# plant-sense.net
KiCad netlist of a schematic drawn in EAGLE
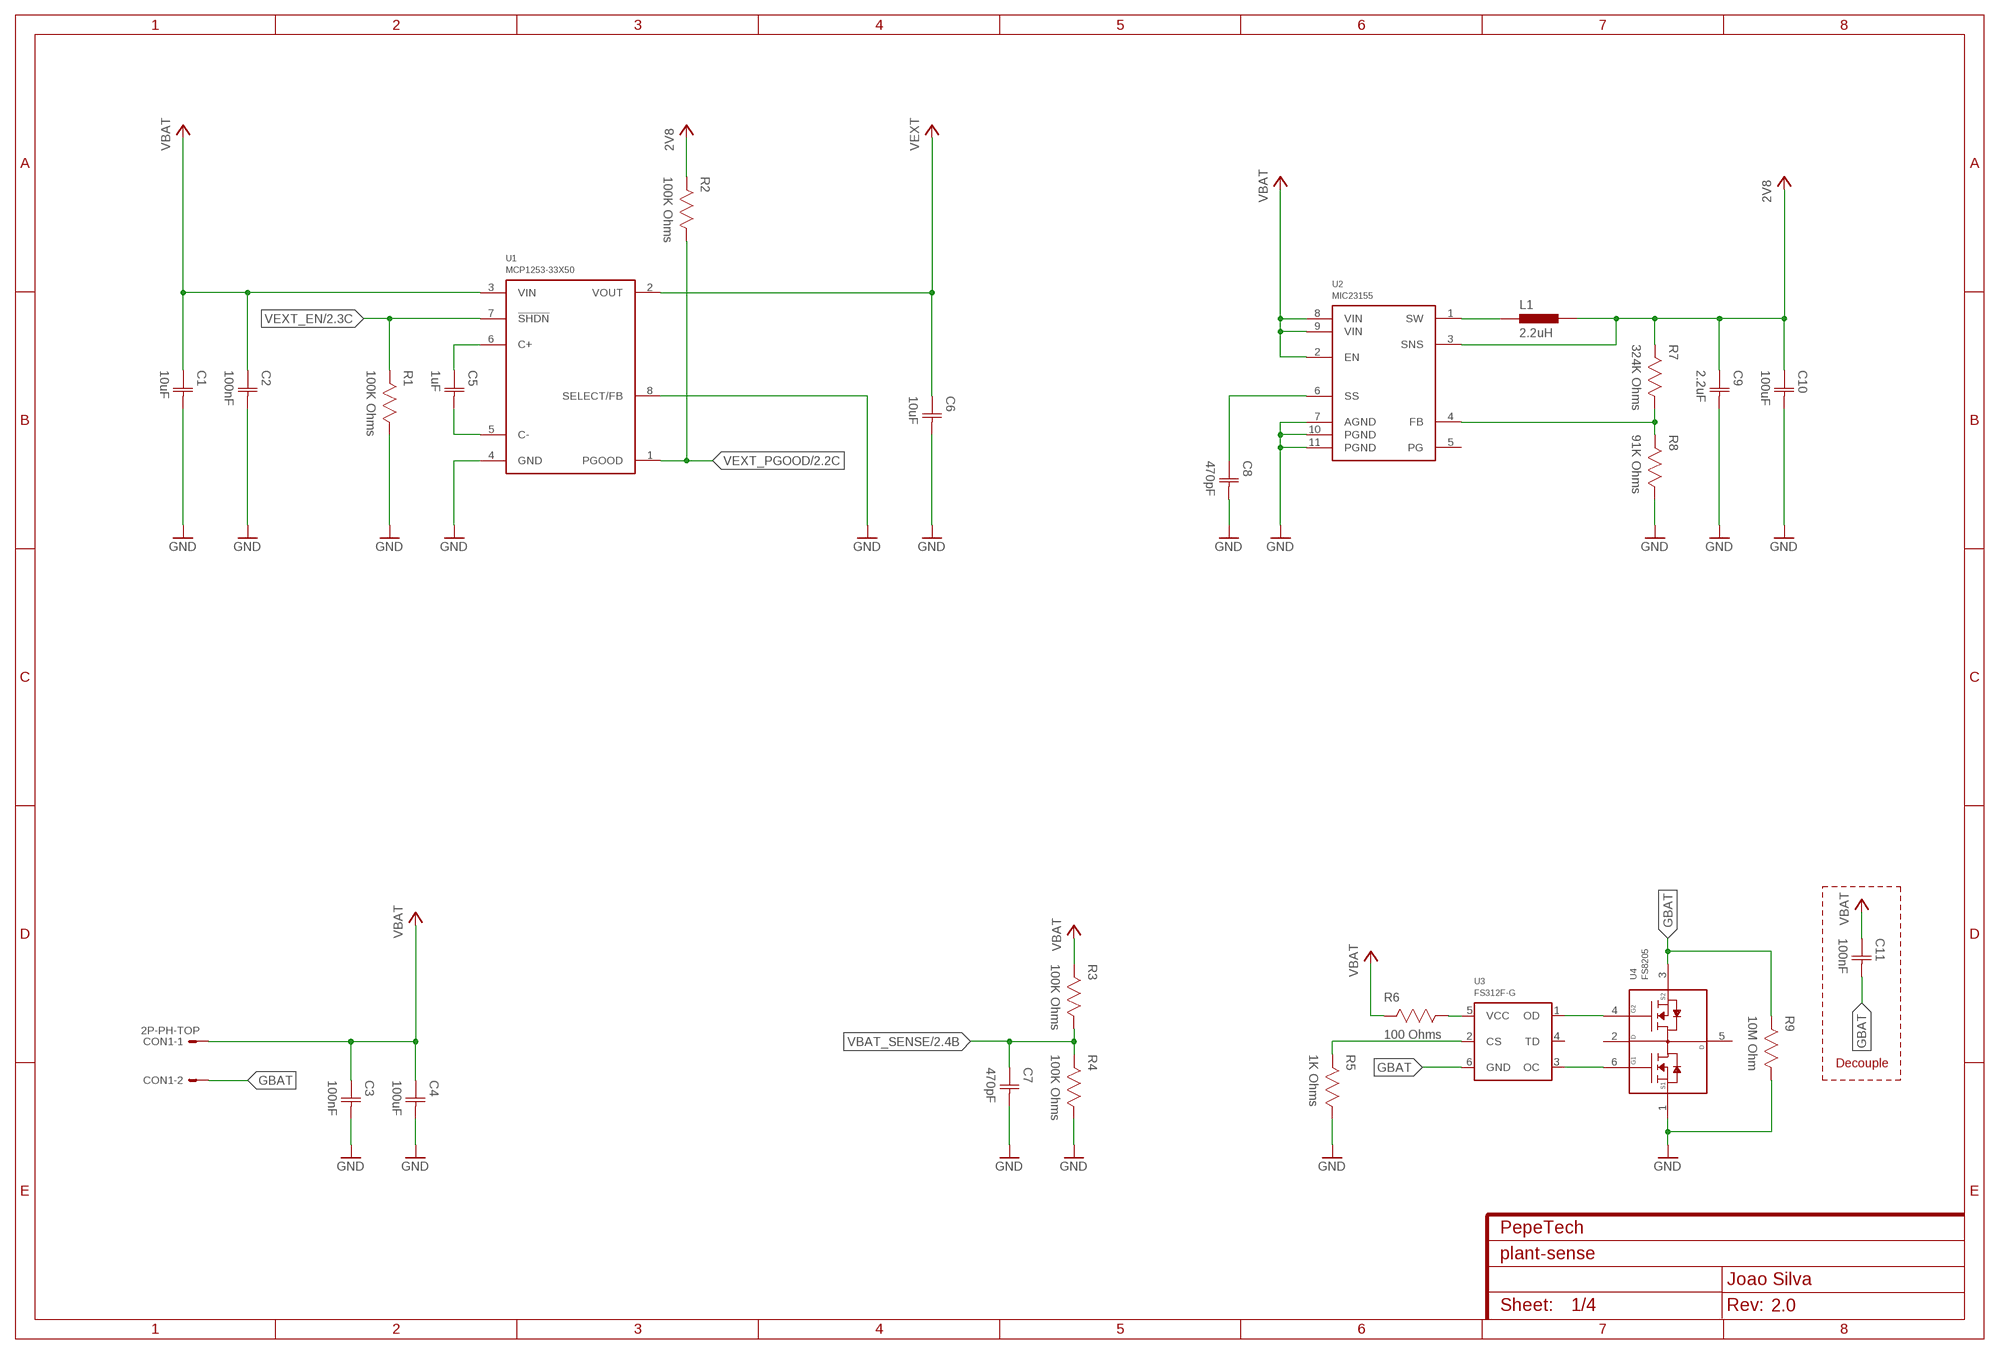
[diagram p0: schematic, sheet 1]
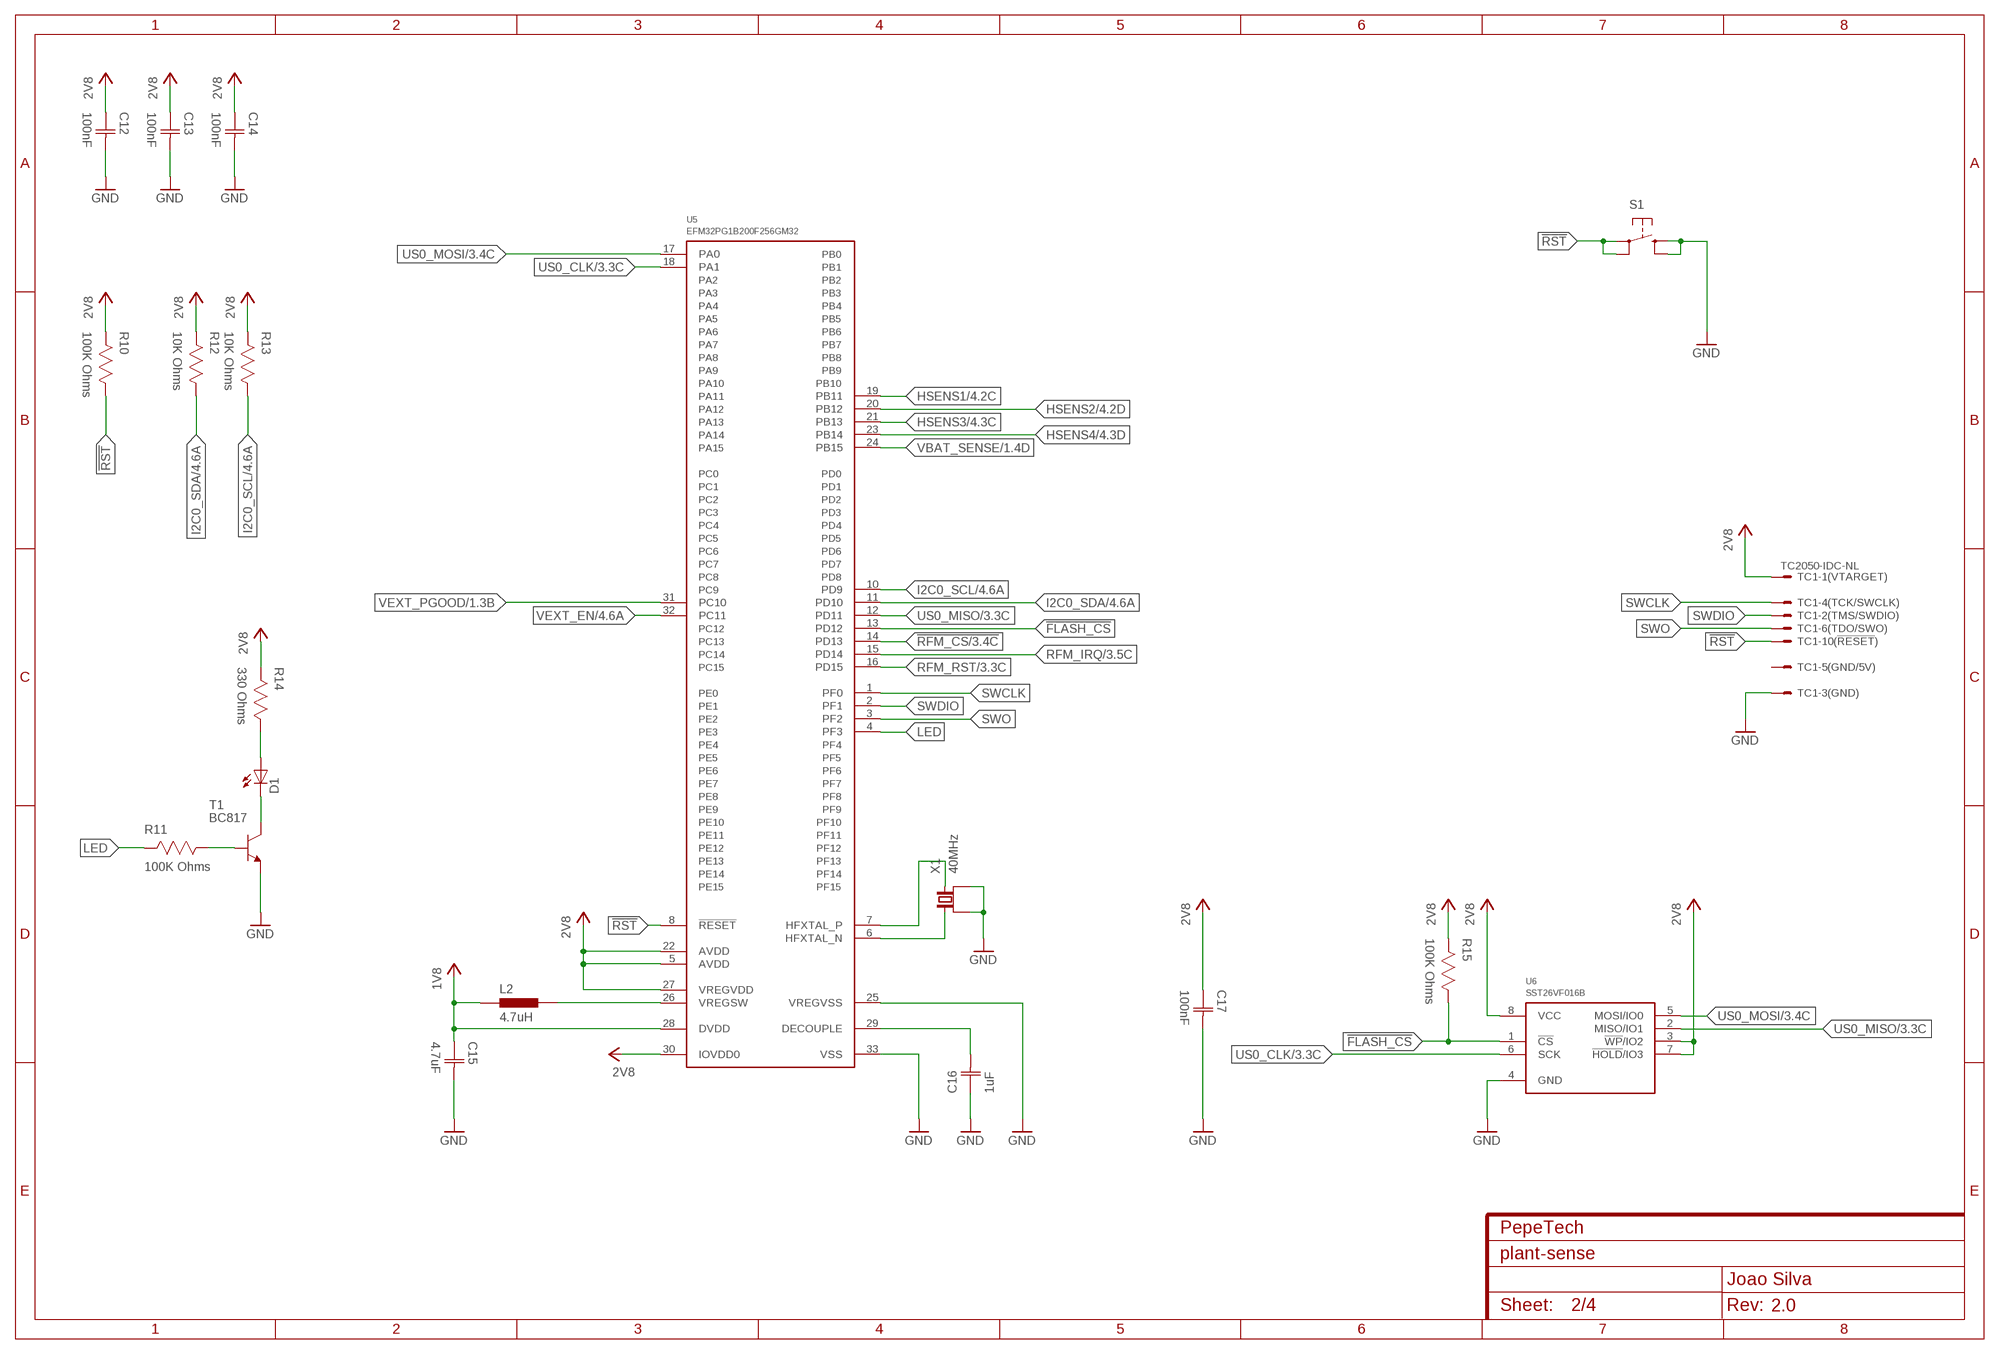
[diagram p1: schematic, sheet 2]
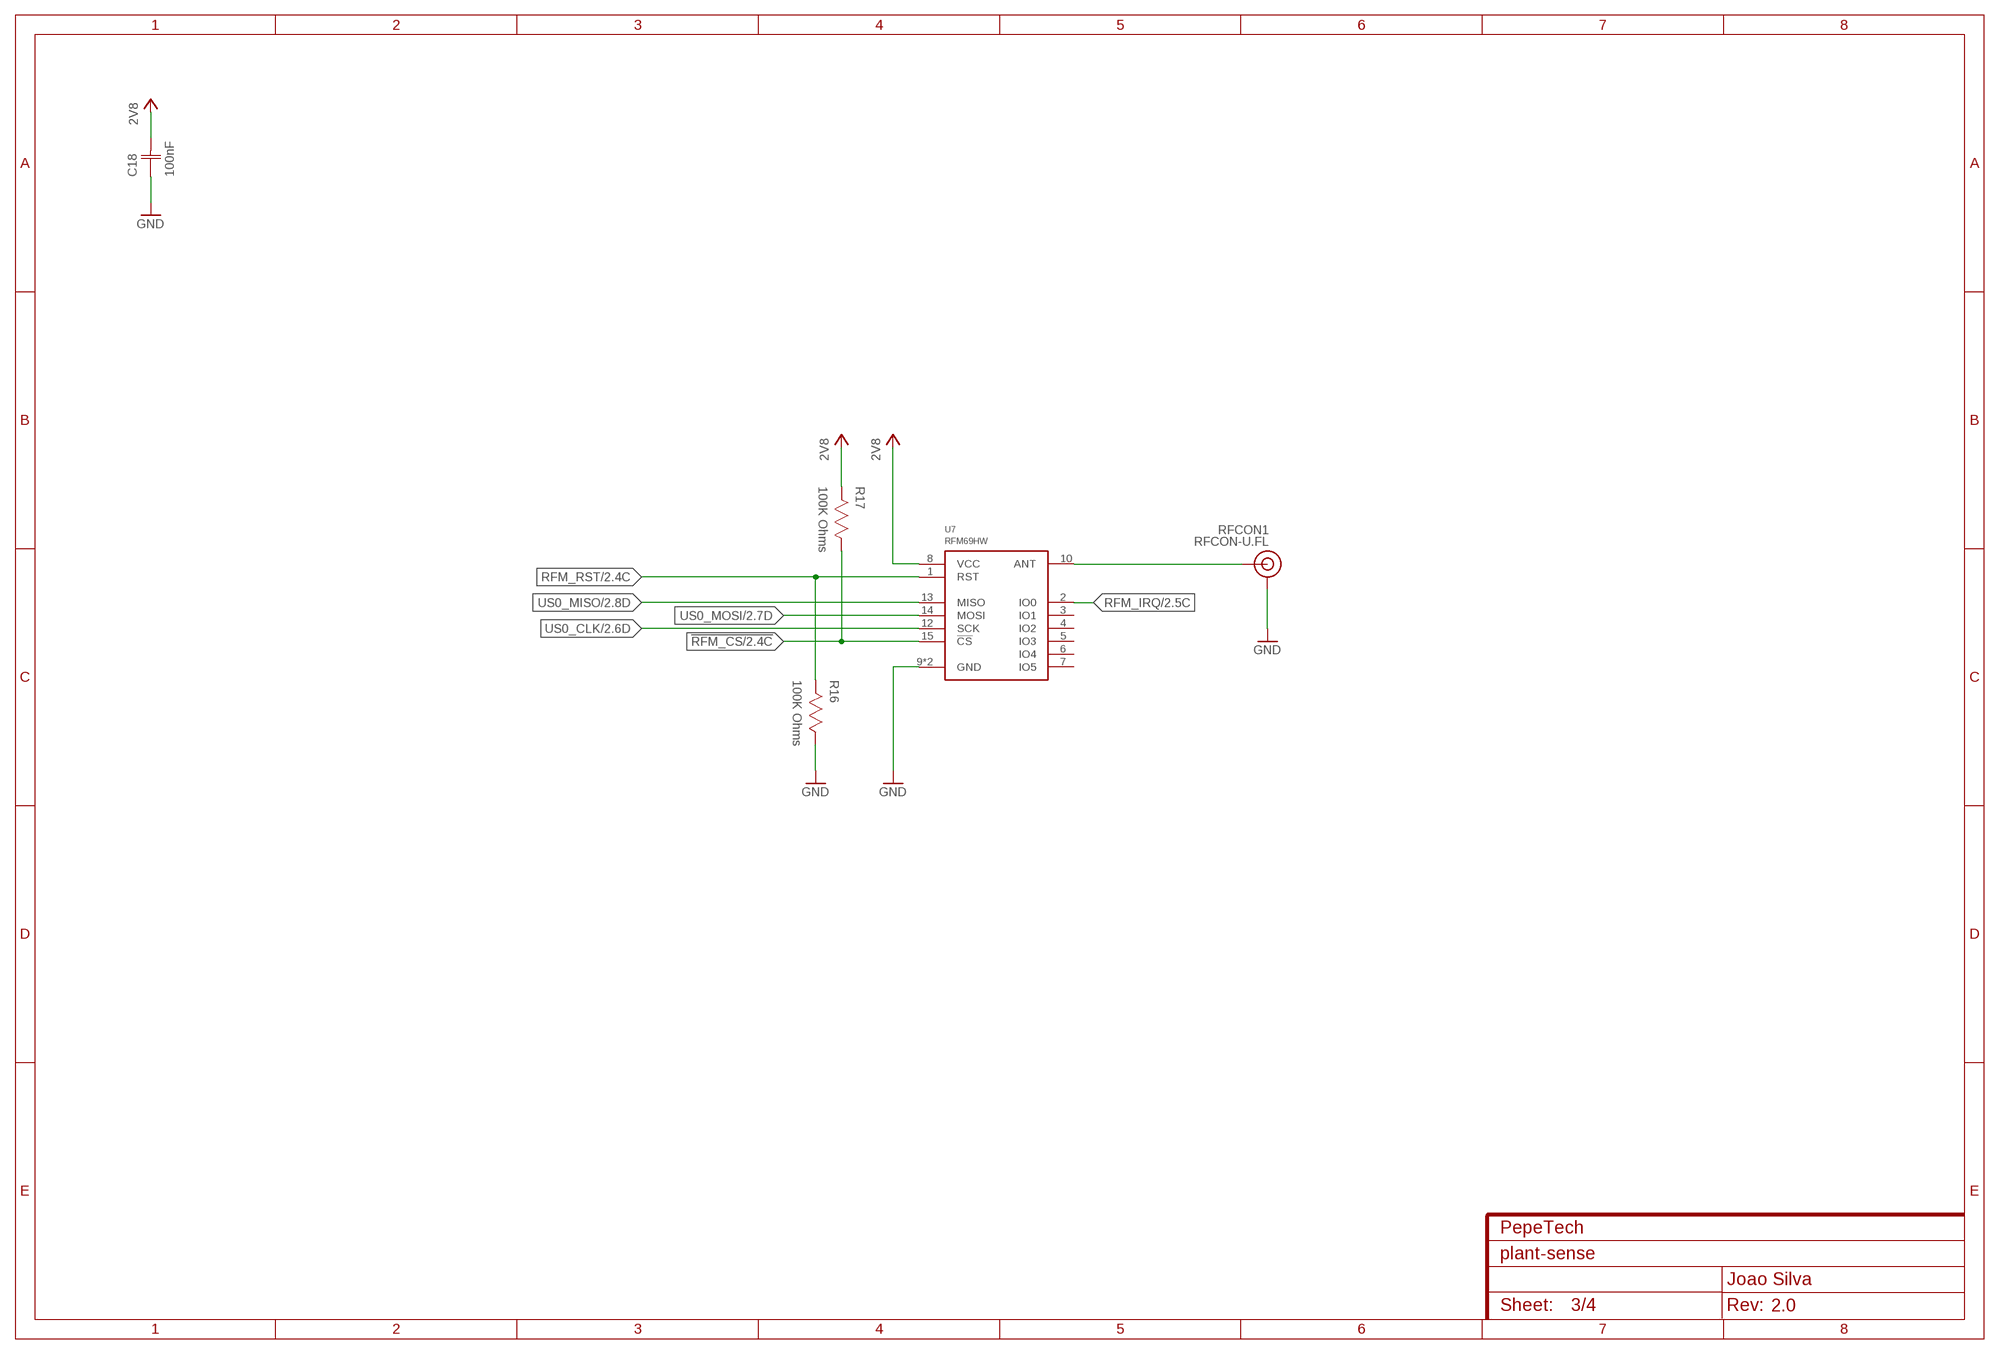
[diagram p2: schematic, sheet 3]
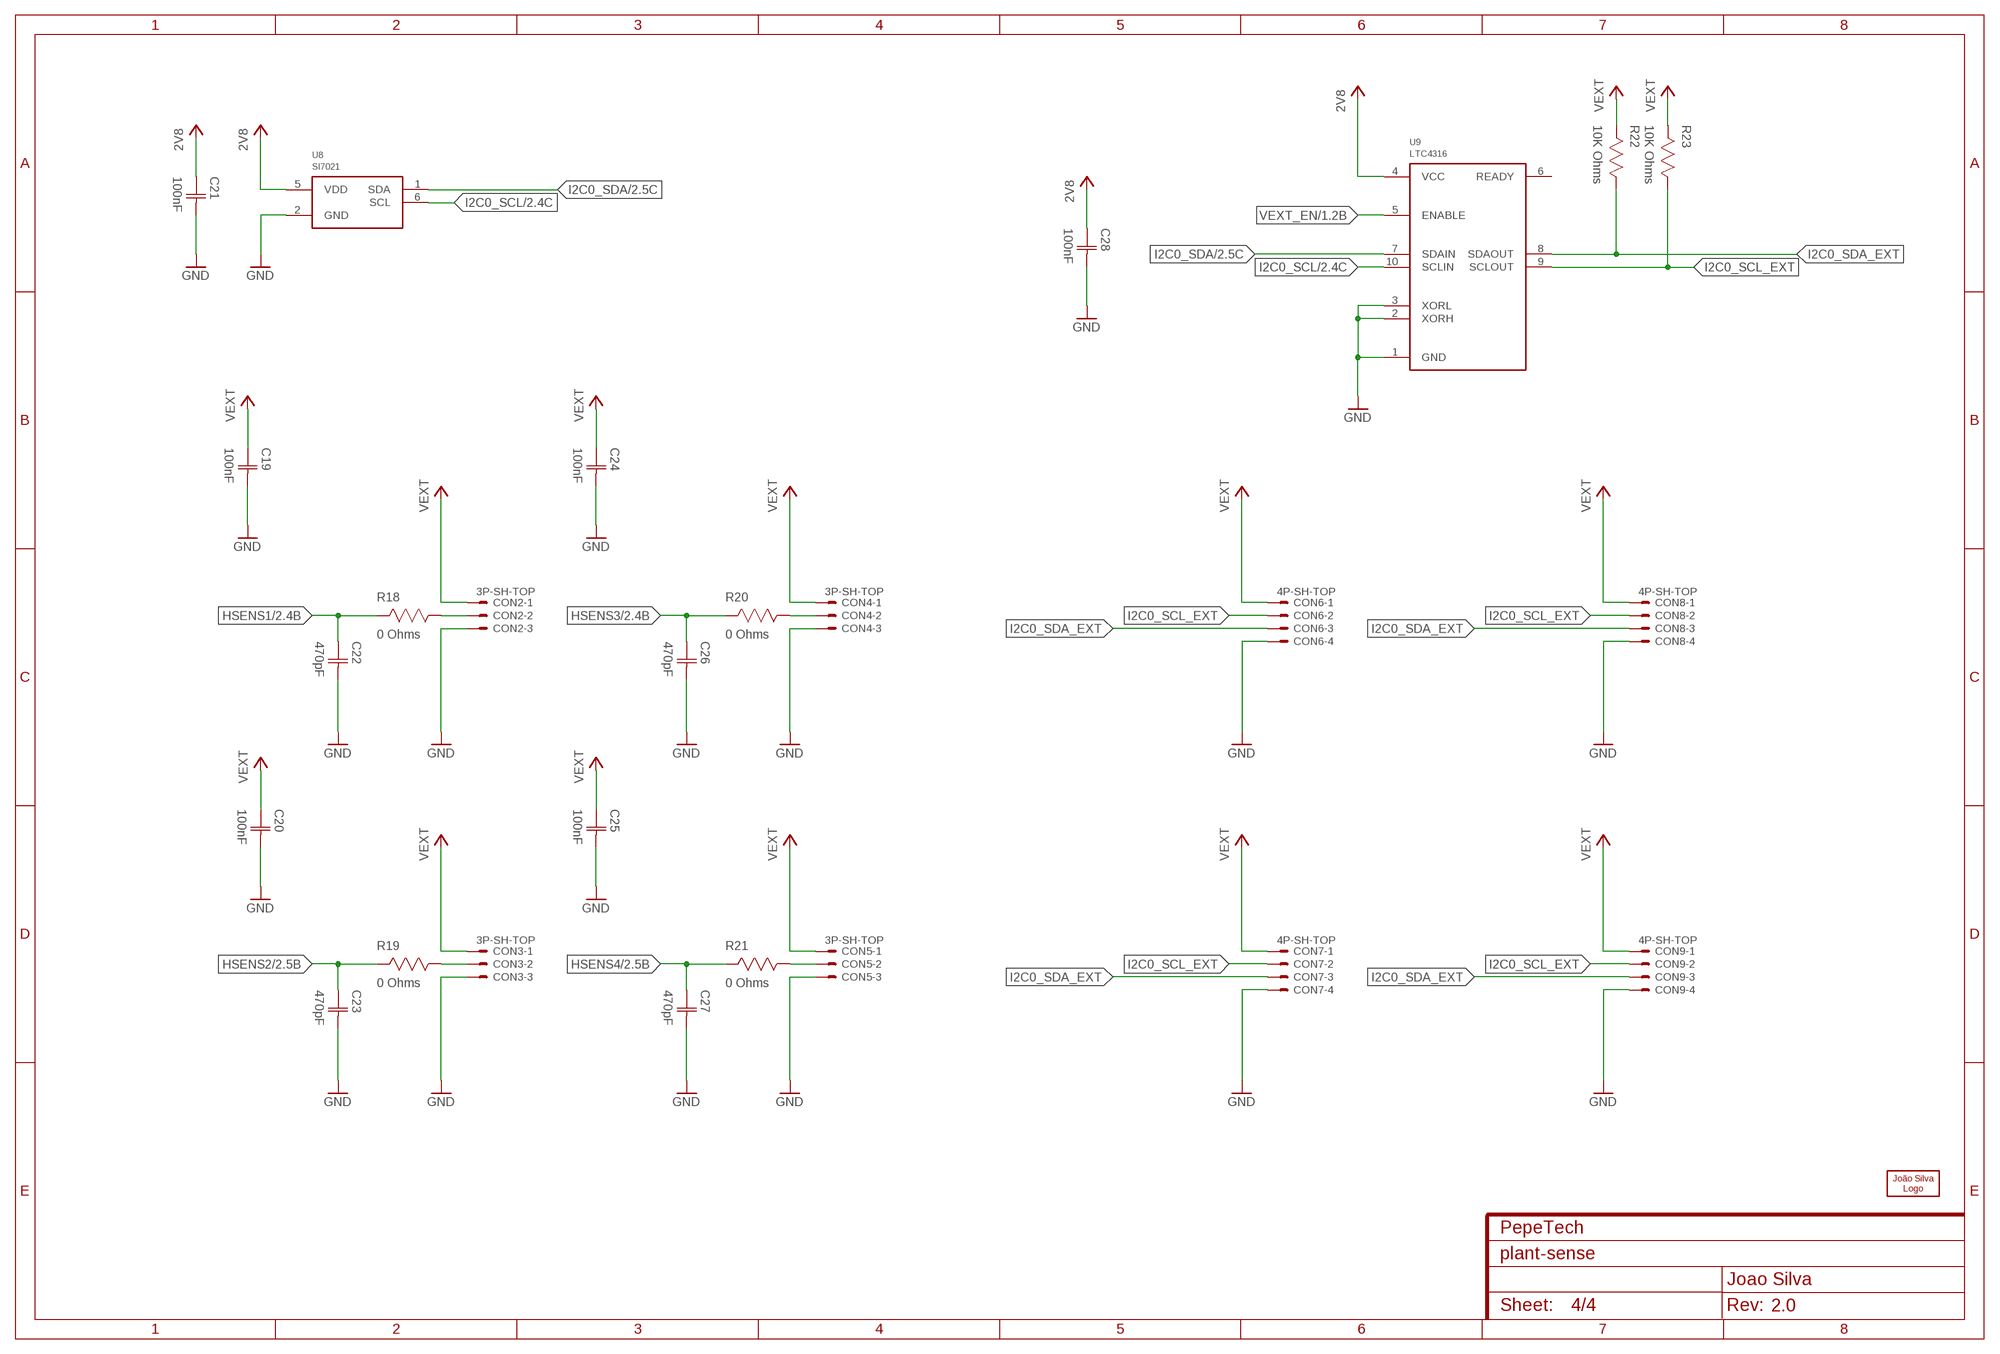
[diagram p3: schematic, sheet 4]

(export (version "E")
  (design (tool "Eeschema 10.0.6"))
  (components
    (comp (ref "C1")
      (value "10uF")
      (footprint "eagle-import:CAP0603")
      (libsource (lib "eagle-import") (part "CAPACITOR-0603"))
    )
    (comp (ref "C2")
      (value "100nF")
      (footprint "eagle-import:CAP0603")
      (libsource (lib "eagle-import") (part "CAPACITOR-0603"))
    )
    (comp (ref "C3")
      (value "100nF")
      (footprint "eagle-import:CAP0603")
      (libsource (lib "eagle-import") (part "CAPACITOR-0603"))
    )
    (comp (ref "C4")
      (value "100uF")
      (footprint "eagle-import:CAP1206")
      (libsource (lib "eagle-import") (part "CAPACITOR-1206"))
    )
    (comp (ref "C5")
      (value "1uF")
      (footprint "eagle-import:CAP0603")
      (libsource (lib "eagle-import") (part "CAPACITOR-0603"))
    )
    (comp (ref "C6")
      (value "10uF")
      (footprint "eagle-import:CAP0603")
      (libsource (lib "eagle-import") (part "CAPACITOR-0603"))
    )
    (comp (ref "C7")
      (value "470pF")
      (footprint "eagle-import:CAP0603")
      (libsource (lib "eagle-import") (part "CAPACITOR-0603"))
    )
    (comp (ref "C8")
      (value "470pF")
      (footprint "eagle-import:CAP0603")
      (libsource (lib "eagle-import") (part "CAPACITOR-0603"))
    )
    (comp (ref "C9")
      (value "2.2uF")
      (footprint "eagle-import:CAP0603")
      (libsource (lib "eagle-import") (part "CAPACITOR-0603"))
    )
    (comp (ref "C10")
      (value "100uF")
      (footprint "eagle-import:CAP1206")
      (libsource (lib "eagle-import") (part "CAPACITOR-1206"))
    )
    (comp (ref "C11")
      (value "100nF")
      (footprint "eagle-import:CAP0603")
      (libsource (lib "eagle-import") (part "CAPACITOR-0603"))
    )
    (comp (ref "CON1")
      (value "2P-PH-TOP")
      (footprint "eagle-import:PH-02-TOP")
      (libsource (lib "eagle-import") (part "2P-PH-TOP"))
    )
    (comp (ref "L1")
      (value "2.2uH")
      (footprint "eagle-import:IND0805")
      (libsource (lib "eagle-import") (part "INDUCTOR-0805"))
    )
    (comp (ref "R1")
      (value "100K Ohms")
      (footprint "eagle-import:RES0603")
      (libsource (lib "eagle-import") (part "RESISTOR-0603"))
    )
    (comp (ref "R2")
      (value "100K Ohms")
      (footprint "eagle-import:RES0603")
      (libsource (lib "eagle-import") (part "RESISTOR-0603"))
    )
    (comp (ref "R3")
      (value "100K Ohms")
      (footprint "eagle-import:RES0603")
      (libsource (lib "eagle-import") (part "RESISTOR-0603"))
    )
    (comp (ref "R4")
      (value "100K Ohms")
      (footprint "eagle-import:RES0603")
      (libsource (lib "eagle-import") (part "RESISTOR-0603"))
    )
    (comp (ref "R5")
      (value "1K Ohms")
      (footprint "eagle-import:RES0603")
      (libsource (lib "eagle-import") (part "RESISTOR-0603"))
    )
    (comp (ref "R6")
      (value "100 Ohms")
      (footprint "eagle-import:RES0603")
      (libsource (lib "eagle-import") (part "RESISTOR-0603"))
    )
    (comp (ref "R7")
      (value "324K Ohms")
      (footprint "eagle-import:RES0603")
      (libsource (lib "eagle-import") (part "RESISTOR-0603"))
    )
    (comp (ref "R8")
      (value "91K Ohms")
      (footprint "eagle-import:RES0603")
      (libsource (lib "eagle-import") (part "RESISTOR-0603"))
    )
    (comp (ref "R9")
      (value "10M Ohm")
      (footprint "eagle-import:RES0603")
      (libsource (lib "eagle-import") (part "RESISTOR-0603"))
    )
    (comp (ref "U1")
      (value "MCP1253-33X50")
      (footprint "eagle-import:MSOP8")
      (libsource (lib "eagle-import") (part "MCP1253-33X50"))
    )
    (comp (ref "U2")
      (value "MIC23155")
      (footprint "eagle-import:DFN10")
      (libsource (lib "eagle-import") (part "MIC23155"))
    )
    (comp (ref "U3")
      (value "FS312F-G")
      (footprint "eagle-import:SOT23-6")
      (libsource (lib "eagle-import") (part "FS312F-G"))
    )
    (comp (ref "U4")
      (value "FS8205")
      (footprint "eagle-import:SOT23-6")
      (libsource (lib "eagle-import") (part "FS8205"))
    )
    (comp (ref "C18")
      (value "100nF")
      (footprint "eagle-import:CAP0603")
      (libsource (lib "eagle-import") (part "CAPACITOR-0603"))
    )
    (comp (ref "R16")
      (value "100K Ohms")
      (footprint "eagle-import:RES0603")
      (libsource (lib "eagle-import") (part "RESISTOR-0603"))
    )
    (comp (ref "R17")
      (value "100K Ohms")
      (footprint "eagle-import:RES0603")
      (libsource (lib "eagle-import") (part "RESISTOR-0603"))
    )
    (comp (ref "RFCON1")
      (value "RFCON-U.FL")
      (footprint "eagle-import:U.FL")
      (libsource (lib "eagle-import") (part "RFCON-U.FL"))
    )
    (comp (ref "U7")
      (value "RFM69HW")
      (footprint "eagle-import:RFM69XW-XXXS2")
      (libsource (lib "eagle-import") (part "RFM69WH"))
    )
    (comp (ref "C19")
      (value "100nF")
      (footprint "eagle-import:CAP0603")
      (libsource (lib "eagle-import") (part "CAPACITOR-0603"))
    )
    (comp (ref "C20")
      (value "100nF")
      (footprint "eagle-import:CAP0603")
      (libsource (lib "eagle-import") (part "CAPACITOR-0603"))
    )
    (comp (ref "C21")
      (value "100nF")
      (footprint "eagle-import:CAP0603")
      (libsource (lib "eagle-import") (part "CAPACITOR-0603"))
    )
    (comp (ref "C22")
      (value "470pF")
      (footprint "eagle-import:CAP0603")
      (libsource (lib "eagle-import") (part "CAPACITOR-0603"))
    )
    (comp (ref "C23")
      (value "470pF")
      (footprint "eagle-import:CAP0603")
      (libsource (lib "eagle-import") (part "CAPACITOR-0603"))
    )
    (comp (ref "C24")
      (value "100nF")
      (footprint "eagle-import:CAP0603")
      (libsource (lib "eagle-import") (part "CAPACITOR-0603"))
    )
    (comp (ref "C25")
      (value "100nF")
      (footprint "eagle-import:CAP0603")
      (libsource (lib "eagle-import") (part "CAPACITOR-0603"))
    )
    (comp (ref "C26")
      (value "470pF")
      (footprint "eagle-import:CAP0603")
      (libsource (lib "eagle-import") (part "CAPACITOR-0603"))
    )
    (comp (ref "C27")
      (value "470pF")
      (footprint "eagle-import:CAP0603")
      (libsource (lib "eagle-import") (part "CAPACITOR-0603"))
    )
    (comp (ref "C28")
      (value "100nF")
      (footprint "eagle-import:CAP0603")
      (libsource (lib "eagle-import") (part "CAPACITOR-0603"))
    )
    (comp (ref "CON2")
      (value "3P-SH-TOP")
      (footprint "eagle-import:SH-03-TOP")
      (libsource (lib "eagle-import") (part "3P-SH-TOP"))
    )
    (comp (ref "CON3")
      (value "3P-SH-TOP")
      (footprint "eagle-import:SH-03-TOP")
      (libsource (lib "eagle-import") (part "3P-SH-TOP"))
    )
    (comp (ref "CON4")
      (value "3P-SH-TOP")
      (footprint "eagle-import:SH-03-TOP")
      (libsource (lib "eagle-import") (part "3P-SH-TOP"))
    )
    (comp (ref "CON5")
      (value "3P-SH-TOP")
      (footprint "eagle-import:SH-03-TOP")
      (libsource (lib "eagle-import") (part "3P-SH-TOP"))
    )
    (comp (ref "CON6")
      (value "4P-SH-TOP")
      (footprint "eagle-import:SH-04-TOP")
      (libsource (lib "eagle-import") (part "4P-SH-TOP"))
    )
    (comp (ref "CON7")
      (value "4P-SH-TOP")
      (footprint "eagle-import:SH-04-TOP")
      (libsource (lib "eagle-import") (part "4P-SH-TOP"))
    )
    (comp (ref "CON8")
      (value "4P-SH-TOP")
      (footprint "eagle-import:SH-04-TOP")
      (libsource (lib "eagle-import") (part "4P-SH-TOP"))
    )
    (comp (ref "CON9")
      (value "4P-SH-TOP")
      (footprint "eagle-import:SH-04-TOP")
      (libsource (lib "eagle-import") (part "4P-SH-TOP"))
    )
    (comp (ref "LOGO1")
      (value "JS-5MM")
      (footprint "eagle-import:JS_5MM")
      (libsource (lib "eagle-import") (part "JS-5MM"))
    )
    (comp (ref "R18")
      (value "0 Ohms")
      (footprint "eagle-import:RES0603")
      (libsource (lib "eagle-import") (part "RESISTOR-0603"))
    )
    (comp (ref "R19")
      (value "0 Ohms")
      (footprint "eagle-import:RES0603")
      (libsource (lib "eagle-import") (part "RESISTOR-0603"))
    )
    (comp (ref "R20")
      (value "0 Ohms")
      (footprint "eagle-import:RES0603")
      (libsource (lib "eagle-import") (part "RESISTOR-0603"))
    )
    (comp (ref "R21")
      (value "0 Ohms")
      (footprint "eagle-import:RES0603")
      (libsource (lib "eagle-import") (part "RESISTOR-0603"))
    )
    (comp (ref "R22")
      (value "10K Ohms")
      (footprint "eagle-import:RES0603")
      (libsource (lib "eagle-import") (part "RESISTOR-0603"))
    )
    (comp (ref "R23")
      (value "10K Ohms")
      (footprint "eagle-import:RES0603")
      (libsource (lib "eagle-import") (part "RESISTOR-0603"))
    )
    (comp (ref "U8")
      (value "SI7021")
      (footprint "eagle-import:DFN6")
      (libsource (lib "eagle-import") (part "SI7021"))
    )
    (comp (ref "U9")
      (value "LTC4316")
      (footprint "eagle-import:MSOP10")
      (libsource (lib "eagle-import") (part "LTC4316"))
    )
    (comp (ref "C12")
      (value "100nF")
      (footprint "eagle-import:CAP0603")
      (libsource (lib "eagle-import") (part "CAPACITOR-0603"))
    )
    (comp (ref "C13")
      (value "100nF")
      (footprint "eagle-import:CAP0603")
      (libsource (lib "eagle-import") (part "CAPACITOR-0603"))
    )
    (comp (ref "C14")
      (value "100nF")
      (footprint "eagle-import:CAP0603")
      (libsource (lib "eagle-import") (part "CAPACITOR-0603"))
    )
    (comp (ref "C15")
      (value "4.7uF")
      (footprint "eagle-import:CAP0603")
      (libsource (lib "eagle-import") (part "CAPACITOR-0603"))
    )
    (comp (ref "C16")
      (value "1uF")
      (footprint "eagle-import:CAP0603")
      (libsource (lib "eagle-import") (part "CAPACITOR-0603"))
    )
    (comp (ref "C17")
      (value "100nF")
      (footprint "eagle-import:CAP0603")
      (libsource (lib "eagle-import") (part "CAPACITOR-0603"))
    )
    (comp (ref "D1")
      (value "LED1206")
      (footprint "eagle-import:1206")
      (libsource (lib "eagle-import") (part "LED1206"))
    )
    (comp (ref "L2")
      (value "4.7uH")
      (footprint "eagle-import:IND0603")
      (libsource (lib "eagle-import") (part "INDUCTOR-0603"))
    )
    (comp (ref "R10")
      (value "100K Ohms")
      (footprint "eagle-import:RES0603")
      (libsource (lib "eagle-import") (part "RESISTOR-0603"))
    )
    (comp (ref "R11")
      (value "100K Ohms")
      (footprint "eagle-import:RES0603")
      (libsource (lib "eagle-import") (part "RESISTOR-0603"))
    )
    (comp (ref "R12")
      (value "10K Ohms")
      (footprint "eagle-import:RES0603")
      (libsource (lib "eagle-import") (part "RESISTOR-0603"))
    )
    (comp (ref "R13")
      (value "10K Ohms")
      (footprint "eagle-import:RES0603")
      (libsource (lib "eagle-import") (part "RESISTOR-0603"))
    )
    (comp (ref "R14")
      (value "330 Ohms")
      (footprint "eagle-import:RES0603")
      (libsource (lib "eagle-import") (part "RESISTOR-0603"))
    )
    (comp (ref "R15")
      (value "100K Ohms")
      (footprint "eagle-import:RES0603")
      (libsource (lib "eagle-import") (part "RESISTOR-0603"))
    )
    (comp (ref "S1")
      (value "TAC_SWITCHSMD")
      (footprint "eagle-import:TAC_SW_SMD_RESET")
      (libsource (lib "eagle-import") (part "TAC_SWITCHSMD"))
    )
    (comp (ref "T1")
      (value "BC817")
      (footprint "eagle-import:SOT23")
      (libsource (lib "eagle-import") (part "BC817"))
    )
    (comp (ref "TC1")
      (value "TC2050-IDC-NL")
      (footprint "eagle-import:TC2050-IDC-NL")
      (libsource (lib "eagle-import") (part "TC2050-IDC-NL"))
    )
    (comp (ref "U5")
      (value "EFM32PG1B200F256GM32")
      (footprint "eagle-import:QFN32_0.5P")
      (libsource (lib "eagle-import") (part "EFM32PG1B200FM32256G"))
    )
    (comp (ref "U6")
      (value "SST26VF016B")
      (footprint "eagle-import:WSOIC8")
      (libsource (lib "eagle-import") (part "SST26VF016B"))
    )
    (comp (ref "X1")
      (value "40MHz")
      (footprint "eagle-import:4-SMD-3225")
      (libsource (lib "eagle-import") (part "CRYSTAL_4P"))
    )
  )
  (nets
    (net (code "1") (name "1V8") (class "Default")
      (node (ref "C15") (pin "1") (pinfunction "C1_1") (pintype "passive"))
      (node (ref "L2") (pin "1") (pinfunction "1_1") (pintype "passive"))
      (node (ref "U5") (pin "28") (pinfunction "DVDD_28") (pintype "bidirectional"))
    )
    (net (code "2") (name "2V8") (class "Default")
      (node (ref "C10") (pin "1") (pinfunction "C1_1") (pintype "passive"))
      (node (ref "C12") (pin "1") (pinfunction "C1_1") (pintype "passive"))
      (node (ref "C13") (pin "1") (pinfunction "C1_1") (pintype "passive"))
      (node (ref "C14") (pin "1") (pinfunction "C1_1") (pintype "passive"))
      (node (ref "C17") (pin "1") (pinfunction "C1_1") (pintype "passive"))
      (node (ref "C18") (pin "2") (pinfunction "C2_2") (pintype "passive"))
      (node (ref "C21") (pin "1") (pinfunction "C1_1") (pintype "passive"))
      (node (ref "C28") (pin "1") (pinfunction "C1_1") (pintype "passive"))
      (node (ref "C9") (pin "1") (pinfunction "C1_1") (pintype "passive"))
      (node (ref "L1") (pin "2") (pinfunction "2_2") (pintype "passive"))
      (node (ref "R10") (pin "2") (pinfunction "2_2") (pintype "passive"))
      (node (ref "R12") (pin "2") (pinfunction "2_2") (pintype "passive"))
      (node (ref "R13") (pin "2") (pinfunction "2_2") (pintype "passive"))
      (node (ref "R14") (pin "2") (pinfunction "2_2") (pintype "passive"))
      (node (ref "R15") (pin "2") (pinfunction "2_2") (pintype "passive"))
      (node (ref "R17") (pin "2") (pinfunction "2_2") (pintype "passive"))
      (node (ref "R2") (pin "2") (pinfunction "2_2") (pintype "passive"))
      (node (ref "R7") (pin "2") (pinfunction "2_2") (pintype "passive"))
      (node (ref "TC1") (pin "1") (pinfunction "S_1") (pintype "passive"))
      (node (ref "U2") (pin "3") (pinfunction "SNS_3") (pintype "bidirectional"))
      (node (ref "U5") (pin "22") (pinfunction "AVDD_22") (pintype "bidirectional"))
      (node (ref "U5") (pin "27") (pinfunction "VREGVDD_27") (pintype "bidirectional"))
      (node (ref "U5") (pin "30") (pinfunction "IOVDD0_30") (pintype "bidirectional"))
      (node (ref "U5") (pin "5") (pinfunction "AVDD_5") (pintype "bidirectional"))
      (node (ref "U6") (pin "3") (pinfunction "~{WP}/IO2_3") (pintype "input"))
      (node (ref "U6") (pin "7") (pinfunction "~{HOLD}/IO3_7") (pintype "input"))
      (node (ref "U6") (pin "8") (pinfunction "VCC_8") (pintype "power_in"))
      (node (ref "U7") (pin "8") (pinfunction "VCC_8") (pintype "power_in"))
      (node (ref "U8") (pin "5") (pinfunction "VDD_5") (pintype "bidirectional"))
      (node (ref "U9") (pin "4") (pinfunction "VCC_4") (pintype "bidirectional"))
    )
    (net (code "3") (name "GBAT") (class "Default")
      (node (ref "C11") (pin "2") (pinfunction "C2_2") (pintype "passive"))
      (node (ref "CON1") (pin "2") (pinfunction "S_2") (pintype "passive"))
      (node (ref "R9") (pin "2") (pinfunction "2_2") (pintype "passive"))
      (node (ref "U3") (pin "6") (pinfunction "GND_6") (pintype "bidirectional"))
      (node (ref "U4") (pin "3") (pinfunction "S2_3") (pintype "bidirectional"))
    )
    (net (code "4") (name "GND") (class "Default")
      (node (ref "C1") (pin "2") (pinfunction "C2_2") (pintype "passive"))
      (node (ref "C10") (pin "2") (pinfunction "C2_2") (pintype "passive"))
      (node (ref "C12") (pin "2") (pinfunction "C2_2") (pintype "passive"))
      (node (ref "C13") (pin "2") (pinfunction "C2_2") (pintype "passive"))
      (node (ref "C14") (pin "2") (pinfunction "C2_2") (pintype "passive"))
      (node (ref "C15") (pin "2") (pinfunction "C2_2") (pintype "passive"))
      (node (ref "C16") (pin "1") (pinfunction "C1_1") (pintype "passive"))
      (node (ref "C17") (pin "2") (pinfunction "C2_2") (pintype "passive"))
      (node (ref "C18") (pin "1") (pinfunction "C1_1") (pintype "passive"))
      (node (ref "C19") (pin "2") (pinfunction "C2_2") (pintype "passive"))
      (node (ref "C2") (pin "2") (pinfunction "C2_2") (pintype "passive"))
      (node (ref "C20") (pin "2") (pinfunction "C2_2") (pintype "passive"))
      (node (ref "C21") (pin "2") (pinfunction "C2_2") (pintype "passive"))
      (node (ref "C22") (pin "2") (pinfunction "C2_2") (pintype "passive"))
      (node (ref "C23") (pin "2") (pinfunction "C2_2") (pintype "passive"))
      (node (ref "C24") (pin "2") (pinfunction "C2_2") (pintype "passive"))
      (node (ref "C25") (pin "2") (pinfunction "C2_2") (pintype "passive"))
      (node (ref "C26") (pin "2") (pinfunction "C2_2") (pintype "passive"))
      (node (ref "C27") (pin "2") (pinfunction "C2_2") (pintype "passive"))
      (node (ref "C28") (pin "2") (pinfunction "C2_2") (pintype "passive"))
      (node (ref "C3") (pin "2") (pinfunction "C2_2") (pintype "passive"))
      (node (ref "C4") (pin "2") (pinfunction "C2_2") (pintype "passive"))
      (node (ref "C6") (pin "2") (pinfunction "C2_2") (pintype "passive"))
      (node (ref "C7") (pin "2") (pinfunction "C2_2") (pintype "passive"))
      (node (ref "C8") (pin "2") (pinfunction "C2_2") (pintype "passive"))
      (node (ref "C9") (pin "2") (pinfunction "C2_2") (pintype "passive"))
      (node (ref "CON2") (pin "3") (pinfunction "S_3") (pintype "passive"))
      (node (ref "CON3") (pin "3") (pinfunction "S_3") (pintype "passive"))
      (node (ref "CON4") (pin "3") (pinfunction "S_3") (pintype "passive"))
      (node (ref "CON5") (pin "3") (pinfunction "S_3") (pintype "passive"))
      (node (ref "CON6") (pin "4") (pinfunction "S_4") (pintype "passive"))
      (node (ref "CON7") (pin "4") (pinfunction "S_4") (pintype "passive"))
      (node (ref "CON8") (pin "4") (pinfunction "S_4") (pintype "passive"))
      (node (ref "CON9") (pin "4") (pinfunction "S_4") (pintype "passive"))
      (node (ref "R1") (pin "1") (pinfunction "1_1") (pintype "passive"))
      (node (ref "R16") (pin "1") (pinfunction "1_1") (pintype "passive"))
      (node (ref "R4") (pin "1") (pinfunction "1_1") (pintype "passive"))
      (node (ref "R5") (pin "1") (pinfunction "1_1") (pintype "passive"))
      (node (ref "R8") (pin "1") (pinfunction "1_1") (pintype "passive"))
      (node (ref "R9") (pin "1") (pinfunction "1_1") (pintype "passive"))
      (node (ref "RFCON1") (pin "P$1") (pinfunction "GND_P$1") (pintype "bidirectional"))
      (node (ref "RFCON1") (pin "P$2") (pinfunction "GND_P$2") (pintype "bidirectional"))
      (node (ref "S1") (pin "3") (pinfunction "3_3") (pintype "passive"))
      (node (ref "S1") (pin "4") (pinfunction "4_4") (pintype "passive"))
      (node (ref "T1") (pin "2") (pinfunction "E_2") (pintype "passive"))
      (node (ref "TC1") (pin "3") (pinfunction "S_3") (pintype "passive"))
      (node (ref "U1") (pin "4") (pinfunction "GND_4") (pintype "bidirectional"))
      (node (ref "U1") (pin "8") (pinfunction "SELECT/FB_8") (pintype "bidirectional"))
      (node (ref "U2") (pin "10") (pinfunction "PGND_10") (pintype "bidirectional"))
      (node (ref "U2") (pin "11") (pinfunction "PGND_11") (pintype "bidirectional"))
      (node (ref "U2") (pin "7") (pinfunction "AGND_7") (pintype "bidirectional"))
      (node (ref "U4") (pin "1") (pinfunction "S1_1") (pintype "bidirectional"))
      (node (ref "U5") (pin "25") (pinfunction "VREGVSS_25") (pintype "bidirectional"))
      (node (ref "U5") (pin "33") (pinfunction "VSS_33") (pintype "bidirectional"))
      (node (ref "U6") (pin "4") (pinfunction "GND_4") (pintype "power_in"))
      (node (ref "U7") (pin "11") (pinfunction "GND_11") (pintype "power_in"))
      (node (ref "U7") (pin "9") (pinfunction "GND_9") (pintype "power_in"))
      (node (ref "U8") (pin "2") (pinfunction "GND_2") (pintype "bidirectional"))
      (node (ref "U9") (pin "1") (pinfunction "GND_1") (pintype "bidirectional"))
      (node (ref "U9") (pin "2") (pinfunction "XORH_2") (pintype "bidirectional"))
      (node (ref "U9") (pin "3") (pinfunction "XORL_3") (pintype "bidirectional"))
      (node (ref "X1") (pin "1") (pinfunction "GND_1") (pintype "passive"))
      (node (ref "X1") (pin "3") (pinfunction "GND_3") (pintype "passive"))
    )
    (net (code "5") (name "HSENS1") (class "Default")
      (node (ref "C22") (pin "1") (pinfunction "C1_1") (pintype "passive"))
      (node (ref "R18") (pin "2") (pinfunction "2_2") (pintype "passive"))
      (node (ref "U5") (pin "19") (pinfunction "PB11_19") (pintype "bidirectional"))
    )
    (net (code "6") (name "HSENS2") (class "Default")
      (node (ref "C23") (pin "1") (pinfunction "C1_1") (pintype "passive"))
      (node (ref "R19") (pin "2") (pinfunction "2_2") (pintype "passive"))
      (node (ref "U5") (pin "20") (pinfunction "PB12_20") (pintype "bidirectional"))
    )
    (net (code "7") (name "HSENS3") (class "Default")
      (node (ref "C26") (pin "1") (pinfunction "C1_1") (pintype "passive"))
      (node (ref "R20") (pin "2") (pinfunction "2_2") (pintype "passive"))
      (node (ref "U5") (pin "21") (pinfunction "PB13_21") (pintype "bidirectional"))
    )
    (net (code "8") (name "HSENS4") (class "Default")
      (node (ref "C27") (pin "1") (pinfunction "C1_1") (pintype "passive"))
      (node (ref "R21") (pin "2") (pinfunction "2_2") (pintype "passive"))
      (node (ref "U5") (pin "23") (pinfunction "PB14_23") (pintype "bidirectional"))
    )
    (net (code "9") (name "I2C0_SCL") (class "Default")
      (node (ref "R13") (pin "1") (pinfunction "1_1") (pintype "passive"))
      (node (ref "U5") (pin "10") (pinfunction "PD9_10") (pintype "bidirectional"))
      (node (ref "U8") (pin "6") (pinfunction "SCL_6") (pintype "bidirectional"))
      (node (ref "U9") (pin "10") (pinfunction "SCLIN_10") (pintype "bidirectional"))
    )
    (net (code "10") (name "I2C0_SCL_EXT") (class "Default")
      (node (ref "CON6") (pin "2") (pinfunction "S_2") (pintype "passive"))
      (node (ref "CON7") (pin "2") (pinfunction "S_2") (pintype "passive"))
      (node (ref "CON8") (pin "2") (pinfunction "S_2") (pintype "passive"))
      (node (ref "CON9") (pin "2") (pinfunction "S_2") (pintype "passive"))
      (node (ref "R23") (pin "1") (pinfunction "1_1") (pintype "passive"))
      (node (ref "U9") (pin "9") (pinfunction "SCLOUT_9") (pintype "bidirectional"))
    )
    (net (code "11") (name "I2C0_SDA") (class "Default")
      (node (ref "R12") (pin "1") (pinfunction "1_1") (pintype "passive"))
      (node (ref "U5") (pin "11") (pinfunction "PD10_11") (pintype "bidirectional"))
      (node (ref "U8") (pin "1") (pinfunction "SDA_1") (pintype "bidirectional"))
      (node (ref "U9") (pin "7") (pinfunction "SDAIN_7") (pintype "bidirectional"))
    )
    (net (code "12") (name "I2C0_SDA_EXT") (class "Default")
      (node (ref "CON6") (pin "3") (pinfunction "S_3") (pintype "passive"))
      (node (ref "CON7") (pin "3") (pinfunction "S_3") (pintype "passive"))
      (node (ref "CON8") (pin "3") (pinfunction "S_3") (pintype "passive"))
      (node (ref "CON9") (pin "3") (pinfunction "S_3") (pintype "passive"))
      (node (ref "R22") (pin "1") (pinfunction "1_1") (pintype "passive"))
      (node (ref "U9") (pin "8") (pinfunction "SDAOUT_8") (pintype "bidirectional"))
    )
    (net (code "13") (name "LED") (class "Default")
      (node (ref "R11") (pin "2") (pinfunction "2_2") (pintype "passive"))
      (node (ref "U5") (pin "4") (pinfunction "PF3_4") (pintype "bidirectional"))
    )
    (net (code "14") (name "Net-(C5-C1)") (class "Default")
      (node (ref "C5") (pin "1") (pinfunction "C1_1") (pintype "passive"))
      (node (ref "U1") (pin "6") (pinfunction "C+_6") (pintype "bidirectional"))
    )
    (net (code "15") (name "Net-(C5-C2)") (class "Default")
      (node (ref "C5") (pin "2") (pinfunction "C2_2") (pintype "passive"))
      (node (ref "U1") (pin "5") (pinfunction "C-_5") (pintype "bidirectional"))
    )
    (net (code "16") (name "Net-(C8-C1)") (class "Default")
      (node (ref "C8") (pin "1") (pinfunction "C1_1") (pintype "passive"))
      (node (ref "U2") (pin "6") (pinfunction "SS_6") (pintype "bidirectional"))
    )
    (net (code "17") (name "Net-(C16-C2)") (class "Default")
      (node (ref "C16") (pin "2") (pinfunction "C2_2") (pintype "passive"))
      (node (ref "U5") (pin "29") (pinfunction "DECOUPLE_29") (pintype "bidirectional"))
    )
    (net (code "18") (name "Net-(CON2B-S)") (class "Default")
      (node (ref "CON2") (pin "2") (pinfunction "S_2") (pintype "passive"))
      (node (ref "R18") (pin "1") (pinfunction "1_1") (pintype "passive"))
    )
    (net (code "19") (name "Net-(CON3B-S)") (class "Default")
      (node (ref "CON3") (pin "2") (pinfunction "S_2") (pintype "passive"))
      (node (ref "R19") (pin "1") (pinfunction "1_1") (pintype "passive"))
    )
    (net (code "20") (name "Net-(CON4B-S)") (class "Default")
      (node (ref "CON4") (pin "2") (pinfunction "S_2") (pintype "passive"))
      (node (ref "R20") (pin "1") (pinfunction "1_1") (pintype "passive"))
    )
    (net (code "21") (name "Net-(CON5B-S)") (class "Default")
      (node (ref "CON5") (pin "2") (pinfunction "S_2") (pintype "passive"))
      (node (ref "R21") (pin "1") (pinfunction "1_1") (pintype "passive"))
    )
    (net (code "22") (name "Net-(D1-PadA)") (class "Default")
      (node (ref "D1") (pin "A") (pinfunction "A_A") (pintype "passive"))
      (node (ref "R14") (pin "1") (pinfunction "1_1") (pintype "passive"))
    )
    (net (code "23") (name "Net-(RFCON1-SIGNAL)") (class "Default")
      (node (ref "RFCON1") (pin "P$3") (pinfunction "SIGNAL_P$3") (pintype "bidirectional"))
      (node (ref "U7") (pin "10") (pinfunction "ANT_10") (pintype "passive"))
    )
    (net (code "24") (name "Net-(T1-B)") (class "Default")
      (node (ref "R11") (pin "1") (pinfunction "1_1") (pintype "passive"))
      (node (ref "T1") (pin "1") (pinfunction "B_1") (pintype "passive"))
    )
    (net (code "25") (name "Net-(T1-C)") (class "Default")
      (node (ref "D1") (pin "C") (pinfunction "C_C") (pintype "passive"))
      (node (ref "T1") (pin "3") (pinfunction "C_3") (pintype "passive"))
    )
    (net (code "26") (name "Net-(U2-FB)") (class "Default")
      (node (ref "R7") (pin "1") (pinfunction "1_1") (pintype "passive"))
      (node (ref "R8") (pin "2") (pinfunction "2_2") (pintype "passive"))
      (node (ref "U2") (pin "4") (pinfunction "FB_4") (pintype "bidirectional"))
    )
    (net (code "27") (name "Net-(U2-SW)") (class "Default")
      (node (ref "L1") (pin "1") (pinfunction "1_1") (pintype "passive"))
      (node (ref "U2") (pin "1") (pinfunction "SW_1") (pintype "bidirectional"))
    )
    (net (code "28") (name "Net-(U3-CS)") (class "Default")
      (node (ref "R5") (pin "2") (pinfunction "2_2") (pintype "passive"))
      (node (ref "U3") (pin "2") (pinfunction "CS_2") (pintype "bidirectional"))
    )
    (net (code "29") (name "Net-(U3-OC)") (class "Default")
      (node (ref "U3") (pin "3") (pinfunction "OC_3") (pintype "bidirectional"))
      (node (ref "U4") (pin "6") (pinfunction "G1_6") (pintype "bidirectional"))
    )
    (net (code "30") (name "Net-(U3-OD)") (class "Default")
      (node (ref "U3") (pin "1") (pinfunction "OD_1") (pintype "bidirectional"))
      (node (ref "U4") (pin "4") (pinfunction "G2_4") (pintype "bidirectional"))
    )
    (net (code "31") (name "Net-(U3-VCC)") (class "Default")
      (node (ref "R6") (pin "1") (pinfunction "1_1") (pintype "passive"))
      (node (ref "U3") (pin "5") (pinfunction "VCC_5") (pintype "bidirectional"))
    )
    (net (code "32") (name "Net-(U5-HFXTAL_N)") (class "Default")
      (node (ref "U5") (pin "6") (pinfunction "HFXTAL_N_6") (pintype "bidirectional"))
      (node (ref "X1") (pin "2") (pinfunction "1_2") (pintype "passive"))
    )
    (net (code "33") (name "Net-(U5-HFXTAL_P)") (class "Default")
      (node (ref "U5") (pin "7") (pinfunction "HFXTAL_P_7") (pintype "bidirectional"))
      (node (ref "X1") (pin "4") (pinfunction "2_4") (pintype "passive"))
    )
    (net (code "34") (name "Net-(U5-VREGSW)") (class "Default")
      (node (ref "L2") (pin "2") (pinfunction "2_2") (pintype "passive"))
      (node (ref "U5") (pin "26") (pinfunction "VREGSW_26") (pintype "bidirectional"))
    )
    (net (code "35") (name "RFM_IRQ") (class "Default")
      (node (ref "U5") (pin "15") (pinfunction "PD14_15") (pintype "bidirectional"))
      (node (ref "U7") (pin "2") (pinfunction "IO0_2") (pintype "bidirectional"))
    )
    (net (code "36") (name "RFM_RST") (class "Default")
      (node (ref "R16") (pin "2") (pinfunction "2_2") (pintype "passive"))
      (node (ref "U5") (pin "16") (pinfunction "PD15_16") (pintype "bidirectional"))
      (node (ref "U7") (pin "1") (pinfunction "RST_1") (pintype "input"))
    )
    (net (code "37") (name "SWCLK") (class "Default")
      (node (ref "TC1") (pin "4") (pinfunction "S_4") (pintype "passive"))
      (node (ref "U5") (pin "1") (pinfunction "PF0_1") (pintype "bidirectional"))
    )
    (net (code "38") (name "SWDIO") (class "Default")
      (node (ref "TC1") (pin "2") (pinfunction "S_2") (pintype "passive"))
      (node (ref "U5") (pin "2") (pinfunction "PF1_2") (pintype "bidirectional"))
    )
    (net (code "39") (name "SWO") (class "Default")
      (node (ref "TC1") (pin "6") (pinfunction "S_6") (pintype "passive"))
      (node (ref "U5") (pin "3") (pinfunction "PF2_3") (pintype "bidirectional"))
    )
    (net (code "40") (name "US0_CLK") (class "Default")
      (node (ref "U5") (pin "18") (pinfunction "PA1_18") (pintype "bidirectional"))
      (node (ref "U6") (pin "6") (pinfunction "SCK_6") (pintype "input"))
      (node (ref "U7") (pin "12") (pinfunction "SCK_12") (pintype "input"))
    )
    (net (code "41") (name "US0_MISO") (class "Default")
      (node (ref "U5") (pin "12") (pinfunction "PD11_12") (pintype "bidirectional"))
      (node (ref "U6") (pin "2") (pinfunction "MISO/IO1_2") (pintype "output"))
      (node (ref "U7") (pin "13") (pinfunction "MISO_13") (pintype "bidirectional"))
    )
    (net (code "42") (name "US0_MOSI") (class "Default")
      (node (ref "U5") (pin "17") (pinfunction "PA0_17") (pintype "bidirectional"))
      (node (ref "U6") (pin "5") (pinfunction "MOSI/IO0_5") (pintype "input"))
      (node (ref "U7") (pin "14") (pinfunction "MOSI_14") (pintype "input"))
    )
    (net (code "43") (name "VBAT") (class "Default")
      (node (ref "C1") (pin "1") (pinfunction "C1_1") (pintype "passive"))
      (node (ref "C11") (pin "1") (pinfunction "C1_1") (pintype "passive"))
      (node (ref "C2") (pin "1") (pinfunction "C1_1") (pintype "passive"))
      (node (ref "C3") (pin "1") (pinfunction "C1_1") (pintype "passive"))
      (node (ref "C4") (pin "1") (pinfunction "C1_1") (pintype "passive"))
      (node (ref "CON1") (pin "1") (pinfunction "S_1") (pintype "passive"))
      (node (ref "R3") (pin "2") (pinfunction "2_2") (pintype "passive"))
      (node (ref "R6") (pin "2") (pinfunction "2_2") (pintype "passive"))
      (node (ref "U1") (pin "3") (pinfunction "VIN_3") (pintype "bidirectional"))
      (node (ref "U2") (pin "2") (pinfunction "EN_2") (pintype "bidirectional"))
      (node (ref "U2") (pin "8") (pinfunction "VIN_8") (pintype "bidirectional"))
      (node (ref "U2") (pin "9") (pinfunction "VIN_9") (pintype "bidirectional"))
    )
    (net (code "44") (name "VBAT_SENSE") (class "Default")
      (node (ref "C7") (pin "1") (pinfunction "C1_1") (pintype "passive"))
      (node (ref "R3") (pin "1") (pinfunction "1_1") (pintype "passive"))
      (node (ref "R4") (pin "2") (pinfunction "2_2") (pintype "passive"))
      (node (ref "U5") (pin "24") (pinfunction "PB15_24") (pintype "bidirectional"))
    )
    (net (code "45") (name "VEXT") (class "Default")
      (node (ref "C19") (pin "1") (pinfunction "C1_1") (pintype "passive"))
      (node (ref "C20") (pin "1") (pinfunction "C1_1") (pintype "passive"))
      (node (ref "C24") (pin "1") (pinfunction "C1_1") (pintype "passive"))
      (node (ref "C25") (pin "1") (pinfunction "C1_1") (pintype "passive"))
      (node (ref "C6") (pin "1") (pinfunction "C1_1") (pintype "passive"))
      (node (ref "CON2") (pin "1") (pinfunction "S_1") (pintype "passive"))
      (node (ref "CON3") (pin "1") (pinfunction "S_1") (pintype "passive"))
      (node (ref "CON4") (pin "1") (pinfunction "S_1") (pintype "passive"))
      (node (ref "CON5") (pin "1") (pinfunction "S_1") (pintype "passive"))
      (node (ref "CON6") (pin "1") (pinfunction "S_1") (pintype "passive"))
      (node (ref "CON7") (pin "1") (pinfunction "S_1") (pintype "passive"))
      (node (ref "CON8") (pin "1") (pinfunction "S_1") (pintype "passive"))
      (node (ref "CON9") (pin "1") (pinfunction "S_1") (pintype "passive"))
      (node (ref "R22") (pin "2") (pinfunction "2_2") (pintype "passive"))
      (node (ref "R23") (pin "2") (pinfunction "2_2") (pintype "passive"))
      (node (ref "U1") (pin "2") (pinfunction "VOUT_2") (pintype "bidirectional"))
    )
    (net (code "46") (name "VEXT_EN") (class "Default")
      (node (ref "R1") (pin "2") (pinfunction "2_2") (pintype "passive"))
      (node (ref "U1") (pin "7") (pinfunction "~{SHDN}_7") (pintype "bidirectional"))
      (node (ref "U5") (pin "32") (pinfunction "PC11_32") (pintype "bidirectional"))
      (node (ref "U9") (pin "5") (pinfunction "ENABLE_5") (pintype "bidirectional"))
    )
    (net (code "47") (name "VEXT_PGOOD") (class "Default")
      (node (ref "R2") (pin "1") (pinfunction "1_1") (pintype "passive"))
      (node (ref "U1") (pin "1") (pinfunction "PGOOD_1") (pintype "bidirectional"))
      (node (ref "U5") (pin "31") (pinfunction "PC10_31") (pintype "bidirectional"))
    )
    (net (code "48") (name "unconnected-(TC1F-S-Pad5)") (class "Default")
      (node (ref "TC1") (pin "5") (pinfunction "S_5") (pintype "passive"))
    )
    (net (code "49") (name "unconnected-(U2-PG-Pad5)") (class "Default")
      (node (ref "U2") (pin "5") (pinfunction "PG_5") (pintype "bidirectional"))
    )
    (net (code "50") (name "unconnected-(U3-TD-Pad4)") (class "Default")
      (node (ref "U3") (pin "4") (pinfunction "TD_4") (pintype "bidirectional"))
    )
    (net (code "51") (name "unconnected-(U4-D12_1-Pad2)") (class "Default")
      (node (ref "U4") (pin "2") (pinfunction "D12_1_2") (pintype "bidirectional"))
    )
    (net (code "52") (name "unconnected-(U4-D12_2-Pad5)") (class "Default")
      (node (ref "U4") (pin "5") (pinfunction "D12_2_5") (pintype "bidirectional"))
    )
    (net (code "53") (name "unconnected-(U7-IO1-Pad3)") (class "Default")
      (node (ref "U7") (pin "3") (pinfunction "IO1_3") (pintype "bidirectional"))
    )
    (net (code "54") (name "unconnected-(U7-IO2-Pad4)") (class "Default")
      (node (ref "U7") (pin "4") (pinfunction "IO2_4") (pintype "bidirectional"))
    )
    (net (code "55") (name "unconnected-(U7-IO3-Pad5)") (class "Default")
      (node (ref "U7") (pin "5") (pinfunction "IO3_5") (pintype "bidirectional"))
    )
    (net (code "56") (name "unconnected-(U7-IO4-Pad6)") (class "Default")
      (node (ref "U7") (pin "6") (pinfunction "IO4_6") (pintype "bidirectional"))
    )
    (net (code "57") (name "unconnected-(U7-IO5-Pad7)") (class "Default")
      (node (ref "U7") (pin "7") (pinfunction "IO5_7") (pintype "bidirectional"))
    )
    (net (code "58") (name "unconnected-(U9-READY-Pad6)") (class "Default")
      (node (ref "U9") (pin "6") (pinfunction "READY_6") (pintype "bidirectional"))
    )
    (net (code "59") (name "~{FLASH_CS}") (class "Default")
      (node (ref "R15") (pin "1") (pinfunction "1_1") (pintype "passive"))
      (node (ref "U5") (pin "13") (pinfunction "PD12_13") (pintype "bidirectional"))
      (node (ref "U6") (pin "1") (pinfunction "~{CS}_1") (pintype "input"))
    )
    (net (code "60") (name "~{RFM_CS}") (class "Default")
      (node (ref "R17") (pin "1") (pinfunction "1_1") (pintype "passive"))
      (node (ref "U5") (pin "14") (pinfunction "PD13_14") (pintype "bidirectional"))
      (node (ref "U7") (pin "15") (pinfunction "~{CS}_15") (pintype "input"))
    )
    (net (code "61") (name "~{RST}") (class "Default")
      (node (ref "R10") (pin "1") (pinfunction "1_1") (pintype "passive"))
      (node (ref "S1") (pin "1") (pinfunction "1_1") (pintype "passive"))
      (node (ref "S1") (pin "2") (pinfunction "2_2") (pintype "passive"))
      (node (ref "TC1") (pin "10") (pinfunction "S_10") (pintype "passive"))
      (node (ref "U5") (pin "8") (pinfunction "~{RESET}_8") (pintype "bidirectional"))
    )
  )
)
